# Onion_Omega_Debug_PCB.net
KiCad netlist of a schematic drawn in Altium Designer
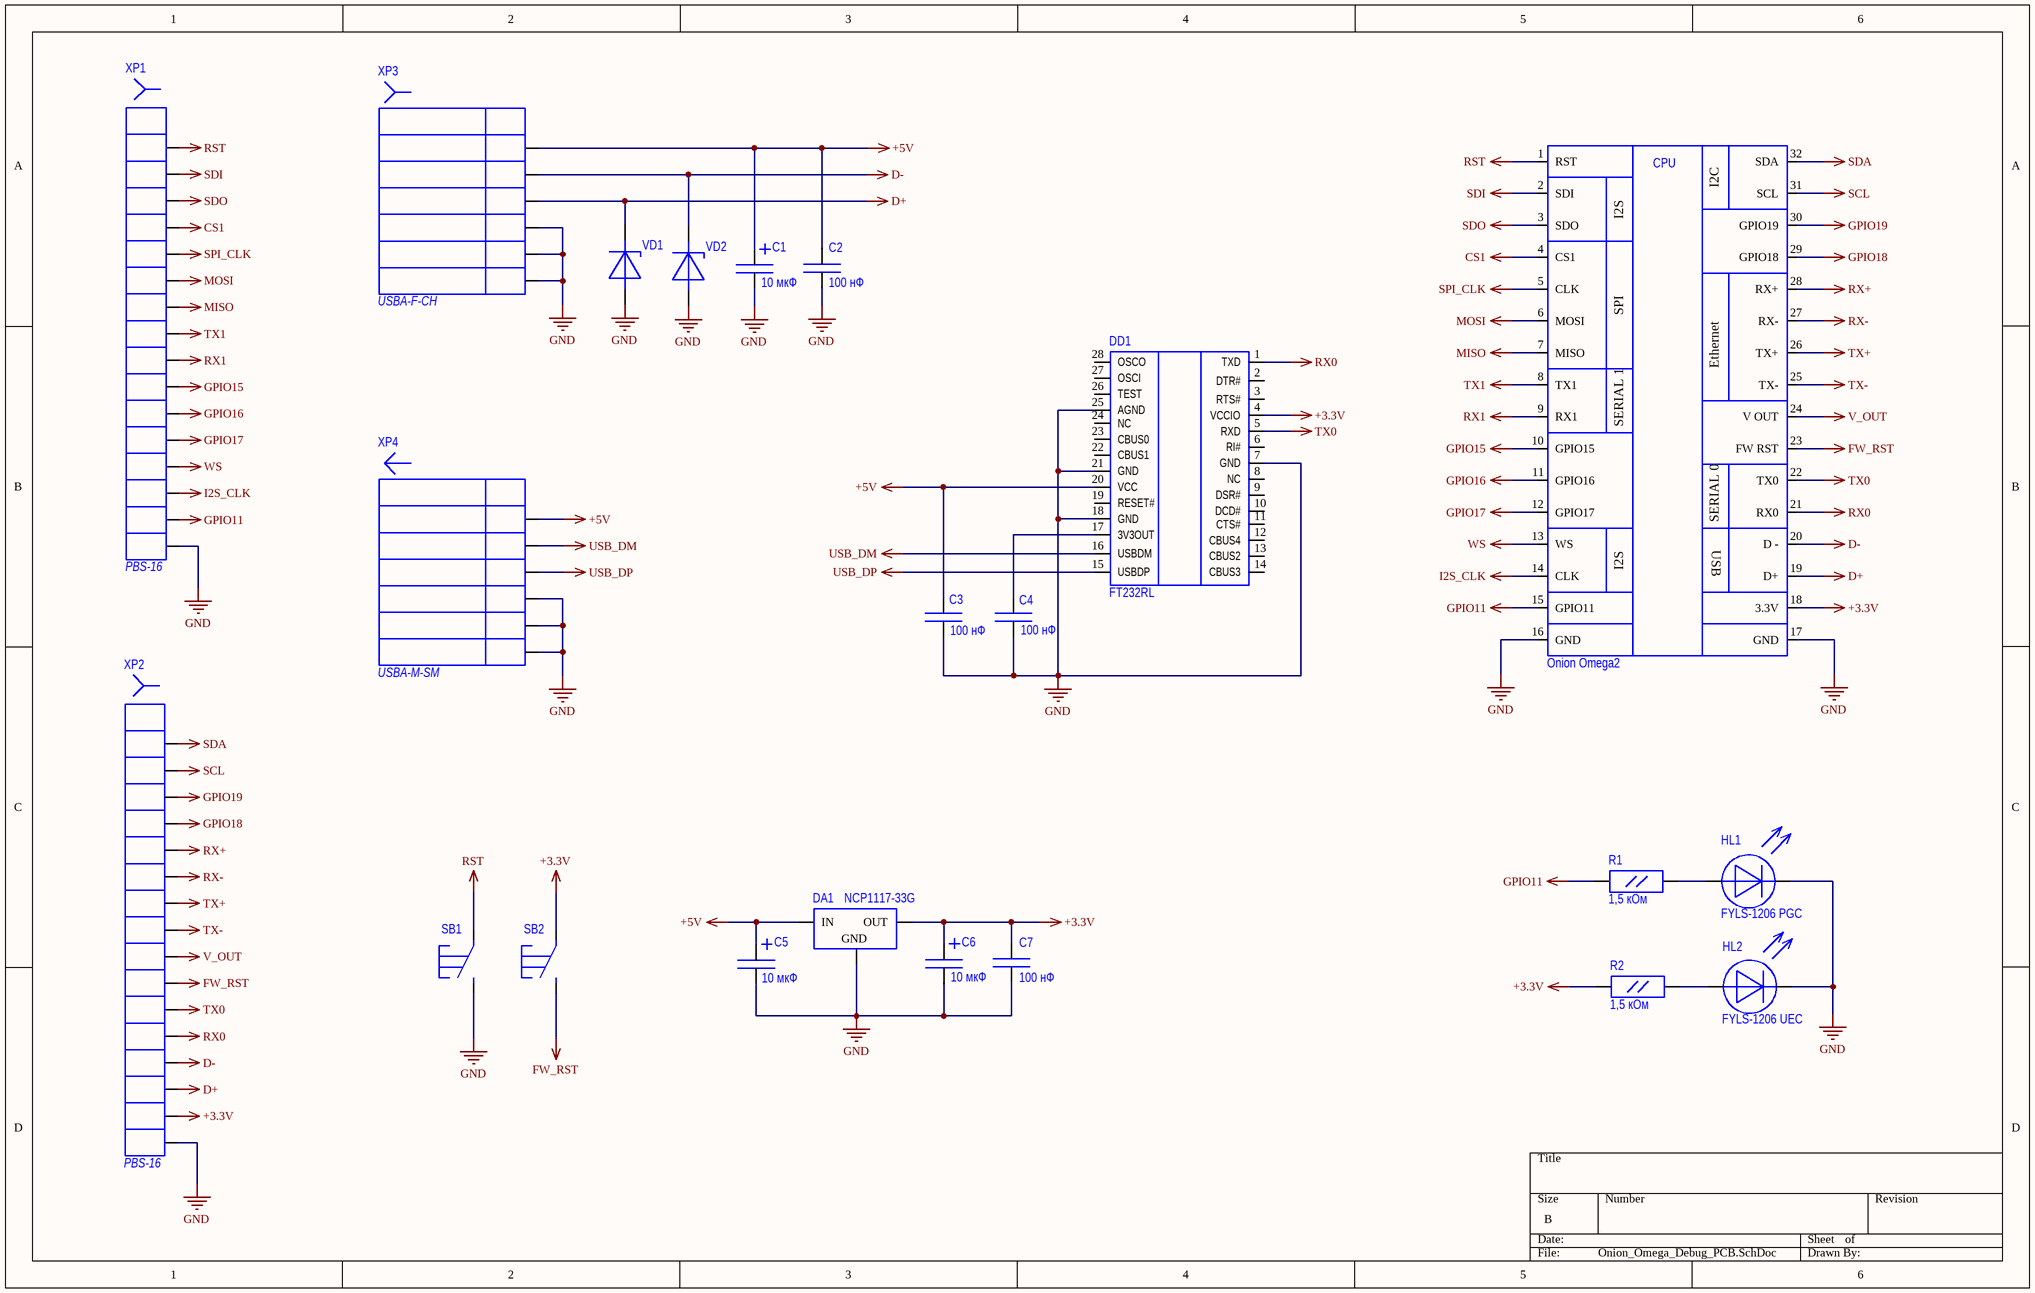
[diagram p0: Onion_Omega_Debug_PCB.SchDoc]

(export (version "E")
  (design (tool "Eeschema 10.0.6"))
  (components
    (comp (ref "C1")
      (value "10 мкФ")
      (footprint "A-case")
      (description "10 мкФ 10 В 10% тип А")
      (fields (field (name "PART NUMBER") "A-case"))
      (libsource (lib "Database") (part "CAPP"))
    )
    (comp (ref "C2")
      (value "100 нФ")
      (footprint "CAP0805")
      (description "100 нФ  5% X7R")
      (libsource (lib "Database") (part "CAP"))
    )
    (comp (ref "C3")
      (value "100 нФ")
      (footprint "CAP0805")
      (description "100 нФ  5% X7R")
      (libsource (lib "Database") (part "CAP"))
    )
    (comp (ref "C4")
      (value "100 нФ")
      (footprint "CAP0805")
      (description "100 нФ  5% X7R")
      (libsource (lib "Database") (part "CAP"))
    )
    (comp (ref "C5")
      (value "10 мкФ")
      (footprint "A-case")
      (description "10 мкФ 10 В 10% тип А")
      (fields (field (name "PART NUMBER") "A-case"))
      (libsource (lib "Database") (part "CAPP"))
    )
    (comp (ref "C6")
      (value "10 мкФ")
      (footprint "A-case")
      (description "10 мкФ 10 В 10% тип А")
      (fields (field (name "PART NUMBER") "A-case"))
      (libsource (lib "Database") (part "CAPP"))
    )
    (comp (ref "C7")
      (value "100 нФ")
      (footprint "CAP0805")
      (description "100 нФ  5% X7R")
      (libsource (lib "Database") (part "CAP"))
    )
    (comp (ref "DA1")
      (value "NCP1117-33G")
      (footprint "D-PAK")
      (libsource (lib "Database") (part "NCP1117-33G"))
    )
    (comp (ref "DD1") (value "FT232RL") (footprint "SSOP-28") (libsource (lib "Database") (part "FT232RL")))
    (comp (ref "HL1")
      (value "FYLS-1206 PGC")
      (footprint "LED 1206 GREEN")
      (description "зеленый сверхяркий")
      (libsource (lib "Database") (part "LED"))
    )
    (comp (ref "HL2")
      (value "FYLS-1206 UЕC")
      (footprint "LED 1206 RED")
      (description "красный")
      (libsource (lib "Database") (part "LED"))
    )
    (comp (ref "OMEGA2")
      (value "Onion Omega2")
      (footprint "Onion_Omega2")
      (libsource (lib "Database") (part "Onion_Omega2"))
    )
    (comp (ref "R1") (value "1,5 кОм") (footprint "RES0805") (libsource (lib "Database") (part "RES 0,125")))
    (comp (ref "R2") (value "1,5 кОм") (footprint "RES0805") (libsource (lib "Database") (part "RES 0,125")))
    (comp (ref "SB1")
      (value "~")
      (footprint "KLS7-TS6606")
      (description "6x6x3.85")
      (fields (field (name "PART NUMBER") "KLS7-TS6606-5.0"))
      (libsource (lib "Database") (part "KLS7-TS6606"))
    )
    (comp (ref "SB2")
      (value "~")
      (footprint "KLS7-TS6606")
      (description "6x6x3.85")
      (fields (field (name "PART NUMBER") "KLS7-TS6606-5.0"))
      (libsource (lib "Database") (part "KLS7-TS6606"))
    )
    (comp (ref "VD1")
      (value "~")
      (footprint "SOT-23")
      (fields (field (name "PART NUMBER") "BZX84-C3V6"))
      (libsource (lib "Database") (part "Zener"))
    )
    (comp (ref "VD2")
      (value "~")
      (footprint "SOT-23")
      (fields (field (name "PART NUMBER") "BZX84-C3V6"))
      (libsource (lib "Database") (part "Zener"))
    )
    (comp (ref "XP1")
      (value "PBS-16")
      (footprint "PBS-16")
      (fields (field (name "PART NUMBER") "PBS-16 2.54mm"))
      (libsource (lib "Database") (part "PBS-16"))
    )
    (comp (ref "XP2")
      (value "PBS-16")
      (footprint "PBS-16")
      (fields (field (name "PART NUMBER") "PBS-16 2.54mm"))
      (libsource (lib "Database") (part "PBS-16"))
    )
    (comp (ref "XP3")
      (value "USBA-F-CH")
      (footprint "USBA-F-CH")
      (fields (field (name "PART NUMBER") "разъем USBA-F-CH"))
      (libsource (lib "Database") (part "USBA-F-CH"))
    )
    (comp (ref "XP4")
      (value "USBA-M-SM")
      (footprint "USBA-M-SM")
      (fields (field (name "PART NUMBER") "разъем USBA-M-SM"))
      (libsource (lib "Database") (part "USBA-M-SM"))
    )
  )
  (nets
    (net (code "1") (name "+3.3V") (class "Default")
      (node (ref "C6") (pin "1") (pinfunction "1_1") (pintype "passive"))
      (node (ref "C7") (pin "1") (pinfunction "1_1") (pintype "passive"))
      (node (ref "DA1") (pin "2") (pinfunction "OUT_2") (pintype "power_in"))
      (node (ref "DD1") (pin "4") (pinfunction "VCCIO_4") (pintype "passive"))
      (node (ref "OMEGA2") (pin "18") (pinfunction "3.3V_18") (pintype "passive"))
      (node (ref "R2") (pin "2") (pinfunction "2_2") (pintype "passive"))
      (node (ref "SB2") (pin "1") (pinfunction "1_1") (pintype "passive"))
      (node (ref "XP2") (pin "15") (pinfunction "15_15") (pintype "passive"))
    )
    (net (code "2") (name "+5V") (class "Default")
      (node (ref "C1") (pin "1") (pinfunction "1_1") (pintype "passive"))
      (node (ref "C2") (pin "1") (pinfunction "1_1") (pintype "passive"))
      (node (ref "C3") (pin "1") (pinfunction "1_1") (pintype "passive"))
      (node (ref "C5") (pin "1") (pinfunction "1_1") (pintype "passive"))
      (node (ref "DA1") (pin "3") (pinfunction "IN_3") (pintype "power_in"))
      (node (ref "DD1") (pin "20") (pinfunction "VCC_20") (pintype "passive"))
      (node (ref "XP3") (pin "1") (pintype "passive"))
      (node (ref "XP4") (pin "1") (pintype "passive"))
    )
    (net (code "3") (name "CS1") (class "Default")
      (node (ref "OMEGA2") (pin "4") (pinfunction "CS1_4") (pintype "passive"))
      (node (ref "XP1") (pin "4") (pinfunction "4_4") (pintype "passive"))
    )
    (net (code "4") (name "D+") (class "Default")
      (node (ref "OMEGA2") (pin "19") (pinfunction "D+_19") (pintype "passive"))
      (node (ref "VD1") (pin "3") (pinfunction "C_3") (pintype "passive"))
      (node (ref "XP2") (pin "14") (pinfunction "14_14") (pintype "passive"))
      (node (ref "XP3") (pin "3") (pintype "passive"))
    )
    (net (code "5") (name "D-") (class "Default")
      (node (ref "OMEGA2") (pin "20") (pinfunction "D_-_20") (pintype "passive"))
      (node (ref "VD2") (pin "3") (pinfunction "C_3") (pintype "passive"))
      (node (ref "XP2") (pin "13") (pinfunction "13_13") (pintype "passive"))
      (node (ref "XP3") (pin "2") (pintype "passive"))
    )
    (net (code "6") (name "FW_RST") (class "Default")
      (node (ref "OMEGA2") (pin "23") (pinfunction "FW_RST_23") (pintype "passive"))
      (node (ref "SB2") (pin "2") (pinfunction "2_2") (pintype "passive"))
      (node (ref "XP2") (pin "10") (pinfunction "10_10") (pintype "passive"))
    )
    (net (code "7") (name "GND") (class "Default")
      (node (ref "C1") (pin "2") (pinfunction "2_2") (pintype "passive"))
      (node (ref "C2") (pin "2") (pinfunction "2_2") (pintype "passive"))
      (node (ref "C3") (pin "2") (pinfunction "2_2") (pintype "passive"))
      (node (ref "C4") (pin "1") (pinfunction "1_1") (pintype "passive"))
      (node (ref "C5") (pin "2") (pinfunction "2_2") (pintype "passive"))
      (node (ref "C6") (pin "2") (pinfunction "2_2") (pintype "passive"))
      (node (ref "C7") (pin "2") (pinfunction "2_2") (pintype "passive"))
      (node (ref "DA1") (pin "1") (pinfunction "GND_1") (pintype "power_in"))
      (node (ref "DD1") (pin "18") (pinfunction "GND_18") (pintype "passive"))
      (node (ref "DD1") (pin "21") (pinfunction "GND_21") (pintype "passive"))
      (node (ref "DD1") (pin "25") (pinfunction "AGND_25") (pintype "passive"))
      (node (ref "DD1") (pin "7") (pinfunction "GND_7") (pintype "passive"))
      (node (ref "HL1") (pin "2") (pinfunction "C_2") (pintype "passive"))
      (node (ref "HL2") (pin "2") (pinfunction "C_2") (pintype "passive"))
      (node (ref "OMEGA2") (pin "16") (pinfunction "GND_16") (pintype "passive"))
      (node (ref "OMEGA2") (pin "17") (pinfunction "GND_17") (pintype "passive"))
      (node (ref "SB1") (pin "2") (pinfunction "2_2") (pintype "passive"))
      (node (ref "VD1") (pin "1") (pinfunction "A_1") (pintype "passive"))
      (node (ref "VD2") (pin "1") (pinfunction "A_1") (pintype "passive"))
      (node (ref "XP1") (pin "16") (pinfunction "16_16") (pintype "passive"))
      (node (ref "XP2") (pin "16") (pinfunction "16_16") (pintype "passive"))
      (node (ref "XP3") (pin "4") (pintype "passive"))
      (node (ref "XP3") (pin "5") (pintype "passive"))
      (node (ref "XP3") (pin "6") (pintype "passive"))
      (node (ref "XP4") (pin "4") (pintype "passive"))
      (node (ref "XP4") (pin "5") (pintype "passive"))
      (node (ref "XP4") (pin "6") (pintype "passive"))
    )
    (net (code "8") (name "GPIO11") (class "Default")
      (node (ref "OMEGA2") (pin "15") (pinfunction "GPIO11_15") (pintype "passive"))
      (node (ref "R1") (pin "1") (pinfunction "1_1") (pintype "passive"))
      (node (ref "XP1") (pin "15") (pinfunction "15_15") (pintype "passive"))
    )
    (net (code "9") (name "GPIO15") (class "Default")
      (node (ref "OMEGA2") (pin "10") (pinfunction "GPIO15_10") (pintype "passive"))
      (node (ref "XP1") (pin "10") (pinfunction "10_10") (pintype "passive"))
    )
    (net (code "10") (name "GPIO16") (class "Default")
      (node (ref "OMEGA2") (pin "11") (pinfunction "GPIO16_11") (pintype "passive"))
      (node (ref "XP1") (pin "11") (pinfunction "11_11") (pintype "passive"))
    )
    (net (code "11") (name "GPIO17") (class "Default")
      (node (ref "OMEGA2") (pin "12") (pinfunction "GPIO17_12") (pintype "passive"))
      (node (ref "XP1") (pin "12") (pinfunction "12_12") (pintype "passive"))
    )
    (net (code "12") (name "GPIO18") (class "Default")
      (node (ref "OMEGA2") (pin "29") (pinfunction "GPIO18_29") (pintype "passive"))
      (node (ref "XP2") (pin "4") (pinfunction "4_4") (pintype "passive"))
    )
    (net (code "13") (name "GPIO19") (class "Default")
      (node (ref "OMEGA2") (pin "30") (pinfunction "GPIO19_30") (pintype "passive"))
      (node (ref "XP2") (pin "3") (pinfunction "3_3") (pintype "passive"))
    )
    (net (code "14") (name "I2S_CLK") (class "Default")
      (node (ref "OMEGA2") (pin "14") (pinfunction "CLK_14") (pintype "passive"))
      (node (ref "XP1") (pin "14") (pinfunction "14_14") (pintype "passive"))
    )
    (net (code "15") (name "MISO") (class "Default")
      (node (ref "OMEGA2") (pin "7") (pinfunction "MISO_7") (pintype "passive"))
      (node (ref "XP1") (pin "7") (pinfunction "7_7") (pintype "passive"))
    )
    (net (code "16") (name "MOSI") (class "Default")
      (node (ref "OMEGA2") (pin "6") (pinfunction "MOSI_6") (pintype "passive"))
      (node (ref "XP1") (pin "6") (pinfunction "6_6") (pintype "passive"))
    )
    (net (code "17") (name "Net-(DD1-3V3OUT)") (class "Default")
      (node (ref "C4") (pin "2") (pinfunction "2_2") (pintype "passive"))
      (node (ref "DD1") (pin "17") (pinfunction "3V3OUT_17") (pintype "passive"))
    )
    (net (code "18") (name "Net-(HL1-A)") (class "Default")
      (node (ref "HL1") (pin "1") (pinfunction "A_1") (pintype "passive"))
      (node (ref "R1") (pin "2") (pinfunction "2_2") (pintype "passive"))
    )
    (net (code "19") (name "Net-(HL2-A)") (class "Default")
      (node (ref "HL2") (pin "1") (pinfunction "A_1") (pintype "passive"))
      (node (ref "R2") (pin "1") (pinfunction "1_1") (pintype "passive"))
    )
    (net (code "20") (name "RST") (class "Default")
      (node (ref "OMEGA2") (pin "1") (pinfunction "RST_1") (pintype "passive"))
      (node (ref "SB1") (pin "1") (pinfunction "1_1") (pintype "passive"))
      (node (ref "XP1") (pin "1") (pinfunction "1_1") (pintype "passive"))
    )
    (net (code "21") (name "RX+") (class "Default")
      (node (ref "OMEGA2") (pin "28") (pinfunction "RX+_28") (pintype "passive"))
      (node (ref "XP2") (pin "5") (pinfunction "5_5") (pintype "passive"))
    )
    (net (code "22") (name "RX-") (class "Default")
      (node (ref "OMEGA2") (pin "27") (pinfunction "RX-_27") (pintype "passive"))
      (node (ref "XP2") (pin "6") (pinfunction "6_6") (pintype "passive"))
    )
    (net (code "23") (name "RX0") (class "Default")
      (node (ref "DD1") (pin "1") (pinfunction "TXD_1") (pintype "passive"))
      (node (ref "OMEGA2") (pin "21") (pinfunction "RX0_21") (pintype "passive"))
      (node (ref "XP2") (pin "12") (pinfunction "12_12") (pintype "passive"))
    )
    (net (code "24") (name "RX1") (class "Default")
      (node (ref "OMEGA2") (pin "9") (pinfunction "RX1_9") (pintype "passive"))
      (node (ref "XP1") (pin "9") (pinfunction "9_9") (pintype "passive"))
    )
    (net (code "25") (name "SCL") (class "Default")
      (node (ref "OMEGA2") (pin "31") (pinfunction "SCL_31") (pintype "passive"))
      (node (ref "XP2") (pin "2") (pinfunction "2_2") (pintype "passive"))
    )
    (net (code "26") (name "SDA") (class "Default")
      (node (ref "OMEGA2") (pin "32") (pinfunction "SDA_32") (pintype "passive"))
      (node (ref "XP2") (pin "1") (pinfunction "1_1") (pintype "passive"))
    )
    (net (code "27") (name "SDI") (class "Default")
      (node (ref "OMEGA2") (pin "2") (pinfunction "SDI_2") (pintype "passive"))
      (node (ref "XP1") (pin "2") (pinfunction "2_2") (pintype "passive"))
    )
    (net (code "28") (name "SDO") (class "Default")
      (node (ref "OMEGA2") (pin "3") (pinfunction "SDO_3") (pintype "passive"))
      (node (ref "XP1") (pin "3") (pinfunction "3_3") (pintype "passive"))
    )
    (net (code "29") (name "SPI_CLK") (class "Default")
      (node (ref "OMEGA2") (pin "5") (pinfunction "CLK_5") (pintype "passive"))
      (node (ref "XP1") (pin "5") (pinfunction "5_5") (pintype "passive"))
    )
    (net (code "30") (name "TX+") (class "Default")
      (node (ref "OMEGA2") (pin "26") (pinfunction "TX+_26") (pintype "passive"))
      (node (ref "XP2") (pin "7") (pinfunction "7_7") (pintype "passive"))
    )
    (net (code "31") (name "TX-") (class "Default")
      (node (ref "OMEGA2") (pin "25") (pinfunction "TX-_25") (pintype "passive"))
      (node (ref "XP2") (pin "8") (pinfunction "8_8") (pintype "passive"))
    )
    (net (code "32") (name "TX0") (class "Default")
      (node (ref "DD1") (pin "5") (pinfunction "RXD_5") (pintype "passive"))
      (node (ref "OMEGA2") (pin "22") (pinfunction "TX0_22") (pintype "passive"))
      (node (ref "XP2") (pin "11") (pinfunction "11_11") (pintype "passive"))
    )
    (net (code "33") (name "TX1") (class "Default")
      (node (ref "OMEGA2") (pin "8") (pinfunction "TX1_8") (pintype "passive"))
      (node (ref "XP1") (pin "8") (pinfunction "8_8") (pintype "passive"))
    )
    (net (code "34") (name "USB_DM") (class "Default")
      (node (ref "DD1") (pin "16") (pinfunction "USBDM_16") (pintype "passive"))
      (node (ref "XP4") (pin "2") (pintype "passive"))
    )
    (net (code "35") (name "USB_DP") (class "Default")
      (node (ref "DD1") (pin "15") (pinfunction "USBDP_15") (pintype "passive"))
      (node (ref "XP4") (pin "3") (pintype "passive"))
    )
    (net (code "36") (name "V_OUT") (class "Default")
      (node (ref "OMEGA2") (pin "24") (pinfunction "V_OUT_24") (pintype "passive"))
      (node (ref "XP2") (pin "9") (pinfunction "9_9") (pintype "passive"))
    )
    (net (code "37") (name "WS") (class "Default")
      (node (ref "OMEGA2") (pin "13") (pinfunction "WS_13") (pintype "passive"))
      (node (ref "XP1") (pin "13") (pinfunction "13_13") (pintype "passive"))
    )
    (net (code "38") (name "unconnected-(DD1-CBUS0-Pad23)") (class "Default")
      (node (ref "DD1") (pin "23") (pinfunction "CBUS0_23") (pintype "passive"))
    )
    (net (code "39") (name "unconnected-(DD1-CBUS1-Pad22)") (class "Default")
      (node (ref "DD1") (pin "22") (pinfunction "CBUS1_22") (pintype "passive"))
    )
    (net (code "40") (name "unconnected-(DD1-CBUS2-Pad13)") (class "Default")
      (node (ref "DD1") (pin "13") (pinfunction "CBUS2_13") (pintype "passive"))
    )
    (net (code "41") (name "unconnected-(DD1-CBUS3-Pad14)") (class "Default")
      (node (ref "DD1") (pin "14") (pinfunction "CBUS3_14") (pintype "passive"))
    )
    (net (code "42") (name "unconnected-(DD1-CBUS4-Pad12)") (class "Default")
      (node (ref "DD1") (pin "12") (pinfunction "CBUS4_12") (pintype "passive"))
    )
    (net (code "43") (name "unconnected-(DD1-CTS#-Pad11)") (class "Default")
      (node (ref "DD1") (pin "11") (pinfunction "CTS#_11") (pintype "passive"))
    )
    (net (code "44") (name "unconnected-(DD1-DCD#-Pad10)") (class "Default")
      (node (ref "DD1") (pin "10") (pinfunction "DCD#_10") (pintype "passive"))
    )
    (net (code "45") (name "unconnected-(DD1-DSR#-Pad9)") (class "Default")
      (node (ref "DD1") (pin "9") (pinfunction "DSR#_9") (pintype "passive"))
    )
    (net (code "46") (name "unconnected-(DD1-DTR#-Pad2)") (class "Default")
      (node (ref "DD1") (pin "2") (pinfunction "DTR#_2") (pintype "passive"))
    )
    (net (code "47") (name "unconnected-(DD1-NC-Pad8)") (class "Default")
      (node (ref "DD1") (pin "8") (pinfunction "NC_8") (pintype "passive"))
    )
    (net (code "48") (name "unconnected-(DD1-NC-Pad24)") (class "Default")
      (node (ref "DD1") (pin "24") (pinfunction "NC_24") (pintype "passive"))
    )
    (net (code "49") (name "unconnected-(DD1-OSCI-Pad27)") (class "Default")
      (node (ref "DD1") (pin "27") (pinfunction "OSCI_27") (pintype "passive"))
    )
    (net (code "50") (name "unconnected-(DD1-OSCO-Pad28)") (class "Default")
      (node (ref "DD1") (pin "28") (pinfunction "OSCO_28") (pintype "passive"))
    )
    (net (code "51") (name "unconnected-(DD1-RESET#-Pad19)") (class "Default")
      (node (ref "DD1") (pin "19") (pinfunction "RESET#_19") (pintype "passive"))
    )
    (net (code "52") (name "unconnected-(DD1-RI#-Pad6)") (class "Default")
      (node (ref "DD1") (pin "6") (pinfunction "RI#_6") (pintype "passive"))
    )
    (net (code "53") (name "unconnected-(DD1-RTS#-Pad3)") (class "Default")
      (node (ref "DD1") (pin "3") (pinfunction "RTS#_3") (pintype "passive"))
    )
    (net (code "54") (name "unconnected-(DD1-TEST-Pad26)") (class "Default")
      (node (ref "DD1") (pin "26") (pinfunction "TEST_26") (pintype "passive"))
    )
  )
)
